# IOIO.net
KiCad netlist of a schematic drawn in EAGLE
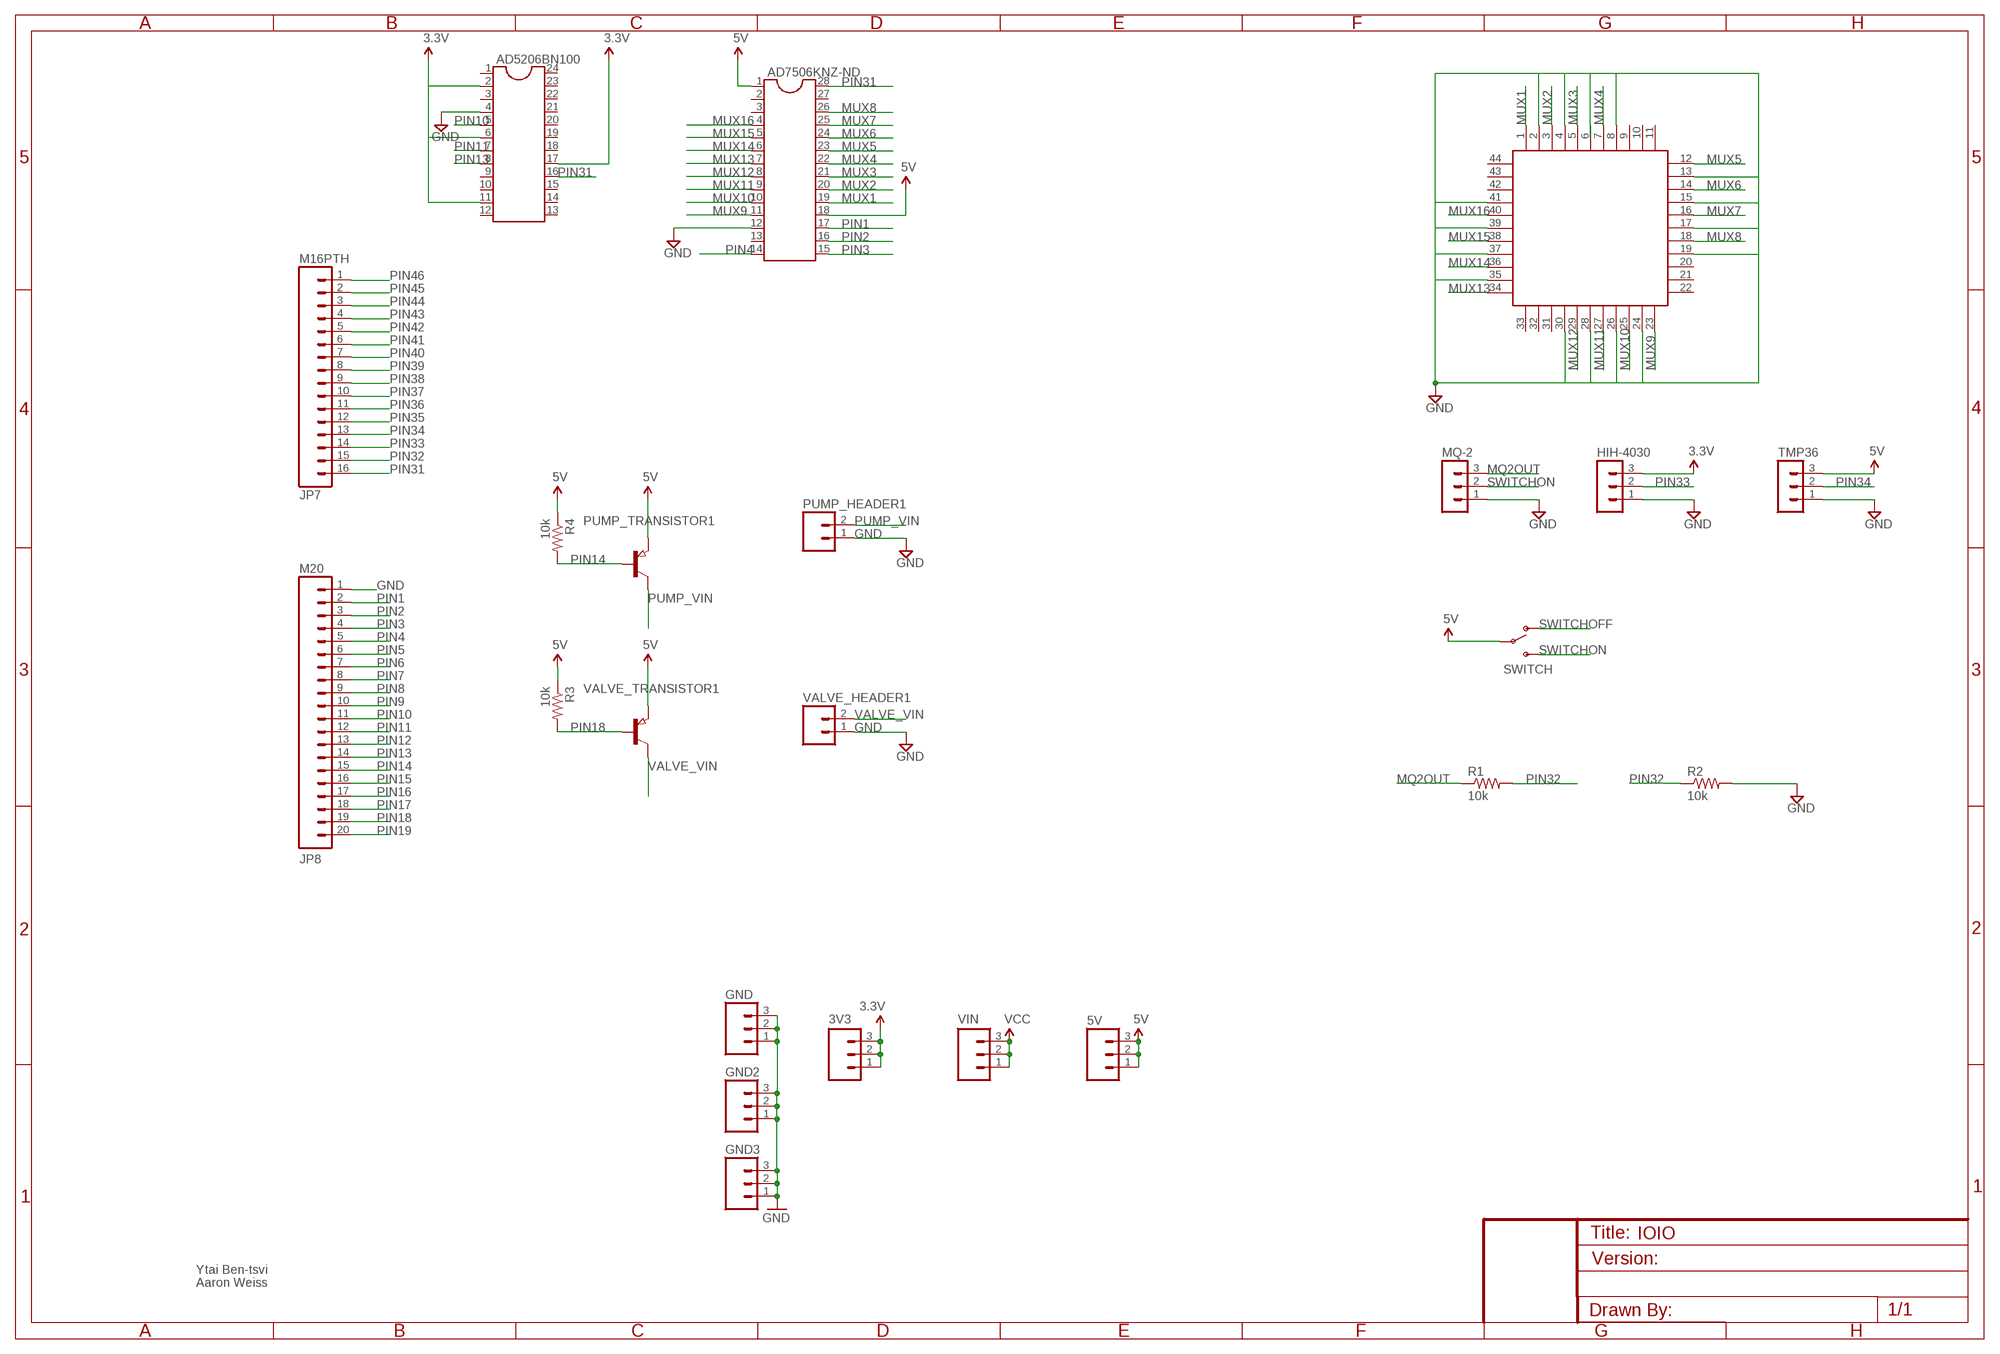
[diagram p0: schematic, sheet 1]

(export (version "E")
  (design (tool "Eeschema 10.0.6"))
  (components
    (comp (ref "3V3")
      (value "M03PTH")
      (footprint "eagle-import:1X03")
      (libsource (lib "eagle-import") (part "M03PTH"))
    )
    (comp (ref "5V")
      (value "M03PTH")
      (footprint "eagle-import:1X03")
      (libsource (lib "eagle-import") (part "M03PTH"))
    )
    (comp (ref "AD5206BN100")
      (value "DIL24-3")
      (footprint "eagle-import:DIL24-3")
      (libsource (lib "eagle-import") (part "DIL24-3"))
    )
    (comp (ref "AD7506KNZ-ND")
      (value "DIL28")
      (footprint "eagle-import:DIL28-6")
      (libsource (lib "eagle-import") (part "DIL28"))
    )
    (comp (ref "GND")
      (value "M03PTH")
      (footprint "eagle-import:1X03")
      (libsource (lib "eagle-import") (part "M03PTH"))
    )
    (comp (ref "GND2")
      (value "M03PTH")
      (footprint "eagle-import:1X03")
      (libsource (lib "eagle-import") (part "M03PTH"))
    )
    (comp (ref "GND3")
      (value "M03PTH")
      (footprint "eagle-import:1X03")
      (libsource (lib "eagle-import") (part "M03PTH"))
    )
    (comp (ref "HIH-4030")
      (value "MA03-1")
      (footprint "eagle-import:MA03-1")
      (libsource (lib "eagle-import") (part "MA03-1"))
    )
    (comp (ref "JP7")
      (value "M16PTH")
      (footprint "eagle-import:1X16")
      (libsource (lib "eagle-import") (part "M16PTH"))
    )
    (comp (ref "JP8")
      (value "M20")
      (footprint "eagle-import:1X20")
      (libsource (lib "eagle-import") (part "M20"))
    )
    (comp (ref "MQ-2")
      (value "MA03-1")
      (footprint "eagle-import:MA03-1")
      (libsource (lib "eagle-import") (part "MA03-1"))
    )
    (comp (ref "PUMP_HEADER1")
      (value "M02PTH")
      (footprint "eagle-import:1X02")
      (libsource (lib "eagle-import") (part "M02PTH"))
    )
    (comp (ref "PUMP_TRANSISTOR1")
      (value "PNP-TRANSISTOR_SOT23")
      (footprint "eagle-import:SOT23")
      (libsource (lib "eagle-import") (part "PNP-TRANSISTOR_SOT23"))
    )
    (comp (ref "R1")
      (value "10k")
      (footprint "eagle-import:0207_7")
      (libsource (lib "eagle-import") (part "R-US_0207/7"))
    )
    (comp (ref "R2")
      (value "10k")
      (footprint "eagle-import:0207_7")
      (libsource (lib "eagle-import") (part "R-US_0207/7"))
    )
    (comp (ref "R3")
      (value "10k")
      (footprint "eagle-import:M2012")
      (libsource (lib "eagle-import") (part "R-US_M2012"))
    )
    (comp (ref "R4")
      (value "10k")
      (footprint "eagle-import:M2012")
      (libsource (lib "eagle-import") (part "R-US_M2012"))
    )
    (comp (ref "SWITCH")
      (value "SWITCH-SPSTPTH")
      (footprint "eagle-import:SWITCH-SPDT")
      (libsource (lib "eagle-import") (part "SWITCH-SPSTPTH"))
    )
    (comp (ref "TMP36")
      (value "MA03-1")
      (footprint "eagle-import:MA03-1")
      (libsource (lib "eagle-import") (part "MA03-1"))
    )
    (comp (ref "U$1")
      (value "S44")
      (footprint "eagle-import:S44")
      (libsource (lib "eagle-import") (part "S44"))
    )
    (comp (ref "VALVE_HEADER1")
      (value "M02PTH")
      (footprint "eagle-import:1X02")
      (libsource (lib "eagle-import") (part "M02PTH"))
    )
    (comp (ref "VALVE_TRANSISTOR1")
      (value "PNP-TRANSISTOR_SOT23")
      (footprint "eagle-import:SOT23")
      (libsource (lib "eagle-import") (part "PNP-TRANSISTOR_SOT23"))
    )
    (comp (ref "VIN")
      (value "M03PTH")
      (footprint "eagle-import:1X03")
      (libsource (lib "eagle-import") (part "M03PTH"))
    )
  )
  (nets
    (net (code "1") (name "/MQ2OUT") (class "Default")
      (node (ref "MQ-2") (pin "3") (pinfunction "3_3") (pintype "passive"))
      (node (ref "R1") (pin "1") (pinfunction "1_1") (pintype "passive"))
    )
    (net (code "2") (name "/MUX1") (class "Default")
      (node (ref "AD7506KNZ-ND") (pin "19") (pinfunction "19_19") (pintype "passive"))
      (node (ref "U$1") (pin "1") (pinfunction "P$1_1") (pintype "bidirectional"))
    )
    (net (code "3") (name "/MUX2") (class "Default")
      (node (ref "AD7506KNZ-ND") (pin "20") (pinfunction "20_20") (pintype "passive"))
      (node (ref "U$1") (pin "3") (pinfunction "P$3_3") (pintype "bidirectional"))
    )
    (net (code "4") (name "/MUX3") (class "Default")
      (node (ref "AD7506KNZ-ND") (pin "21") (pinfunction "21_21") (pintype "passive"))
      (node (ref "U$1") (pin "5") (pinfunction "P$5_5") (pintype "bidirectional"))
    )
    (net (code "5") (name "/MUX4") (class "Default")
      (node (ref "AD7506KNZ-ND") (pin "22") (pinfunction "22_22") (pintype "passive"))
      (node (ref "U$1") (pin "7") (pinfunction "P$7_7") (pintype "bidirectional"))
    )
    (net (code "6") (name "/MUX5") (class "Default")
      (node (ref "AD7506KNZ-ND") (pin "23") (pinfunction "23_23") (pintype "passive"))
      (node (ref "U$1") (pin "12") (pinfunction "P$12_12") (pintype "bidirectional"))
    )
    (net (code "7") (name "/MUX6") (class "Default")
      (node (ref "AD7506KNZ-ND") (pin "24") (pinfunction "24_24") (pintype "passive"))
      (node (ref "U$1") (pin "14") (pinfunction "P$14_14") (pintype "bidirectional"))
    )
    (net (code "8") (name "/MUX7") (class "Default")
      (node (ref "AD7506KNZ-ND") (pin "25") (pinfunction "25_25") (pintype "passive"))
      (node (ref "U$1") (pin "16") (pinfunction "P$16_16") (pintype "bidirectional"))
    )
    (net (code "9") (name "/MUX8") (class "Default")
      (node (ref "AD7506KNZ-ND") (pin "26") (pinfunction "26_26") (pintype "passive"))
      (node (ref "U$1") (pin "18") (pinfunction "P$18_18") (pintype "bidirectional"))
    )
    (net (code "10") (name "/MUX9") (class "Default")
      (node (ref "AD7506KNZ-ND") (pin "11") (pinfunction "11_11") (pintype "passive"))
      (node (ref "U$1") (pin "23") (pinfunction "P$23_23") (pintype "bidirectional"))
    )
    (net (code "11") (name "/MUX10") (class "Default")
      (node (ref "AD7506KNZ-ND") (pin "10") (pinfunction "10_10") (pintype "passive"))
      (node (ref "U$1") (pin "25") (pinfunction "P$25_25") (pintype "bidirectional"))
    )
    (net (code "12") (name "/MUX11") (class "Default")
      (node (ref "AD7506KNZ-ND") (pin "9") (pinfunction "9_9") (pintype "passive"))
      (node (ref "U$1") (pin "27") (pinfunction "P$27_27") (pintype "bidirectional"))
    )
    (net (code "13") (name "/MUX12") (class "Default")
      (node (ref "AD7506KNZ-ND") (pin "8") (pinfunction "8_8") (pintype "passive"))
      (node (ref "U$1") (pin "29") (pinfunction "P$29_29") (pintype "bidirectional"))
    )
    (net (code "14") (name "/MUX13") (class "Default")
      (node (ref "AD7506KNZ-ND") (pin "7") (pinfunction "7_7") (pintype "passive"))
      (node (ref "U$1") (pin "34") (pinfunction "P$34_34") (pintype "bidirectional"))
    )
    (net (code "15") (name "/MUX14") (class "Default")
      (node (ref "AD7506KNZ-ND") (pin "6") (pinfunction "6_6") (pintype "passive"))
      (node (ref "U$1") (pin "36") (pinfunction "P$36_36") (pintype "bidirectional"))
    )
    (net (code "16") (name "/MUX15") (class "Default")
      (node (ref "AD7506KNZ-ND") (pin "5") (pinfunction "5_5") (pintype "passive"))
      (node (ref "U$1") (pin "38") (pinfunction "P$38_38") (pintype "bidirectional"))
    )
    (net (code "17") (name "/MUX16") (class "Default")
      (node (ref "AD7506KNZ-ND") (pin "4") (pinfunction "4_4") (pintype "passive"))
      (node (ref "U$1") (pin "40") (pinfunction "P$40_40") (pintype "bidirectional"))
    )
    (net (code "18") (name "/PIN1") (class "Default")
      (node (ref "AD7506KNZ-ND") (pin "17") (pinfunction "17_17") (pintype "passive"))
      (node (ref "JP8") (pin "2") (pinfunction "2_2") (pintype "passive"))
    )
    (net (code "19") (name "/PIN2") (class "Default")
      (node (ref "AD7506KNZ-ND") (pin "16") (pinfunction "16_16") (pintype "passive"))
      (node (ref "JP8") (pin "3") (pinfunction "3_3") (pintype "passive"))
    )
    (net (code "20") (name "/PIN3") (class "Default")
      (node (ref "AD7506KNZ-ND") (pin "15") (pinfunction "15_15") (pintype "passive"))
      (node (ref "JP8") (pin "4") (pinfunction "4_4") (pintype "passive"))
    )
    (net (code "21") (name "/PIN4") (class "Default")
      (node (ref "AD7506KNZ-ND") (pin "14") (pinfunction "14_14") (pintype "passive"))
      (node (ref "JP8") (pin "5") (pinfunction "5_5") (pintype "passive"))
    )
    (net (code "22") (name "/PIN5") (class "Default")
      (node (ref "JP8") (pin "6") (pinfunction "6_6") (pintype "passive"))
    )
    (net (code "23") (name "/PIN6") (class "Default")
      (node (ref "JP8") (pin "7") (pinfunction "7_7") (pintype "passive"))
    )
    (net (code "24") (name "/PIN7") (class "Default")
      (node (ref "JP8") (pin "8") (pinfunction "8_8") (pintype "passive"))
    )
    (net (code "25") (name "/PIN8") (class "Default")
      (node (ref "JP8") (pin "9") (pinfunction "9_9") (pintype "passive"))
    )
    (net (code "26") (name "/PIN9") (class "Default")
      (node (ref "JP8") (pin "10") (pinfunction "10_10") (pintype "passive"))
    )
    (net (code "27") (name "/PIN10") (class "Default")
      (node (ref "AD5206BN100") (pin "5") (pinfunction "5_5") (pintype "passive"))
      (node (ref "JP8") (pin "11") (pinfunction "11_11") (pintype "passive"))
    )
    (net (code "28") (name "/PIN11") (class "Default")
      (node (ref "AD5206BN100") (pin "7") (pinfunction "7_7") (pintype "passive"))
      (node (ref "JP8") (pin "12") (pinfunction "12_12") (pintype "passive"))
    )
    (net (code "29") (name "/PIN12") (class "Default")
      (node (ref "JP8") (pin "13") (pinfunction "13_13") (pintype "passive"))
    )
    (net (code "30") (name "/PIN13") (class "Default")
      (node (ref "AD5206BN100") (pin "8") (pinfunction "8_8") (pintype "passive"))
      (node (ref "JP8") (pin "14") (pinfunction "14_14") (pintype "passive"))
    )
    (net (code "31") (name "/PIN14") (class "Default")
      (node (ref "JP8") (pin "15") (pinfunction "15_15") (pintype "passive"))
      (node (ref "PUMP_TRANSISTOR1") (pin "1") (pinfunction "B_1") (pintype "passive"))
      (node (ref "R4") (pin "2") (pinfunction "2_2") (pintype "passive"))
    )
    (net (code "32") (name "/PIN15") (class "Default")
      (node (ref "JP8") (pin "16") (pinfunction "16_16") (pintype "passive"))
    )
    (net (code "33") (name "/PIN16") (class "Default")
      (node (ref "JP8") (pin "17") (pinfunction "17_17") (pintype "passive"))
    )
    (net (code "34") (name "/PIN17") (class "Default")
      (node (ref "JP8") (pin "18") (pinfunction "18_18") (pintype "passive"))
    )
    (net (code "35") (name "/PIN18") (class "Default")
      (node (ref "JP8") (pin "19") (pinfunction "19_19") (pintype "passive"))
      (node (ref "R3") (pin "2") (pinfunction "2_2") (pintype "passive"))
      (node (ref "VALVE_TRANSISTOR1") (pin "1") (pinfunction "B_1") (pintype "passive"))
    )
    (net (code "36") (name "/PIN19") (class "Default")
      (node (ref "JP8") (pin "20") (pinfunction "20_20") (pintype "passive"))
    )
    (net (code "37") (name "/PIN31") (class "Default")
      (node (ref "AD5206BN100") (pin "16") (pinfunction "16_16") (pintype "passive"))
      (node (ref "AD7506KNZ-ND") (pin "28") (pinfunction "28_28") (pintype "passive"))
      (node (ref "JP7") (pin "16") (pinfunction "16_16") (pintype "passive"))
    )
    (net (code "38") (name "/PIN32") (class "Default")
      (node (ref "JP7") (pin "15") (pinfunction "15_15") (pintype "passive"))
      (node (ref "R1") (pin "2") (pinfunction "2_2") (pintype "passive"))
      (node (ref "R2") (pin "1") (pinfunction "1_1") (pintype "passive"))
    )
    (net (code "39") (name "/PIN33") (class "Default")
      (node (ref "HIH-4030") (pin "2") (pinfunction "2_2") (pintype "passive"))
      (node (ref "JP7") (pin "14") (pinfunction "14_14") (pintype "passive"))
    )
    (net (code "40") (name "/PIN34") (class "Default")
      (node (ref "JP7") (pin "13") (pinfunction "13_13") (pintype "passive"))
      (node (ref "TMP36") (pin "2") (pinfunction "2_2") (pintype "passive"))
    )
    (net (code "41") (name "/PIN35") (class "Default")
      (node (ref "JP7") (pin "12") (pinfunction "12_12") (pintype "passive"))
    )
    (net (code "42") (name "/PIN36") (class "Default")
      (node (ref "JP7") (pin "11") (pinfunction "11_11") (pintype "passive"))
    )
    (net (code "43") (name "/PIN37") (class "Default")
      (node (ref "JP7") (pin "10") (pinfunction "10_10") (pintype "passive"))
    )
    (net (code "44") (name "/PIN38") (class "Default")
      (node (ref "JP7") (pin "9") (pinfunction "9_9") (pintype "passive"))
    )
    (net (code "45") (name "/PIN39") (class "Default")
      (node (ref "JP7") (pin "8") (pinfunction "8_8") (pintype "passive"))
    )
    (net (code "46") (name "/PIN40") (class "Default")
      (node (ref "JP7") (pin "7") (pinfunction "7_7") (pintype "passive"))
    )
    (net (code "47") (name "/PIN41") (class "Default")
      (node (ref "JP7") (pin "6") (pinfunction "6_6") (pintype "passive"))
    )
    (net (code "48") (name "/PIN42") (class "Default")
      (node (ref "JP7") (pin "5") (pinfunction "5_5") (pintype "passive"))
    )
    (net (code "49") (name "/PIN43") (class "Default")
      (node (ref "JP7") (pin "4") (pinfunction "4_4") (pintype "passive"))
    )
    (net (code "50") (name "/PIN44") (class "Default")
      (node (ref "JP7") (pin "3") (pinfunction "3_3") (pintype "passive"))
    )
    (net (code "51") (name "/PIN45") (class "Default")
      (node (ref "JP7") (pin "2") (pinfunction "2_2") (pintype "passive"))
    )
    (net (code "52") (name "/PIN46") (class "Default")
      (node (ref "JP7") (pin "1") (pinfunction "1_1") (pintype "passive"))
    )
    (net (code "53") (name "/PUMP_VIN") (class "Default")
      (node (ref "PUMP_HEADER1") (pin "2") (pinfunction "2_2") (pintype "passive"))
      (node (ref "PUMP_TRANSISTOR1") (pin "3") (pinfunction "C_3") (pintype "passive"))
    )
    (net (code "54") (name "/SWITCHOFF") (class "Default")
      (node (ref "SWITCH") (pin "1") (pinfunction "O_1") (pintype "passive"))
    )
    (net (code "55") (name "/SWITCHON") (class "Default")
      (node (ref "MQ-2") (pin "2") (pinfunction "2_2") (pintype "passive"))
      (node (ref "SWITCH") (pin "3") (pinfunction "S_3") (pintype "passive"))
    )
    (net (code "56") (name "/VALVE_VIN") (class "Default")
      (node (ref "VALVE_HEADER1") (pin "2") (pinfunction "2_2") (pintype "passive"))
      (node (ref "VALVE_TRANSISTOR1") (pin "3") (pinfunction "C_3") (pintype "passive"))
    )
    (net (code "57") (name "3.3V") (class "Default")
      (node (ref "3V3") (pin "1") (pinfunction "1_1") (pintype "passive"))
      (node (ref "3V3") (pin "2") (pinfunction "2_2") (pintype "passive"))
      (node (ref "3V3") (pin "3") (pinfunction "3_3") (pintype "passive"))
      (node (ref "AD5206BN100") (pin "11") (pinfunction "11_11") (pintype "passive"))
      (node (ref "AD5206BN100") (pin "17") (pinfunction "17_17") (pintype "passive"))
      (node (ref "AD5206BN100") (pin "2") (pinfunction "2_2") (pintype "passive"))
      (node (ref "AD5206BN100") (pin "6") (pinfunction "6_6") (pintype "passive"))
      (node (ref "HIH-4030") (pin "3") (pinfunction "3_3") (pintype "passive"))
    )
    (net (code "58") (name "5V") (class "Default")
      (node (ref "5V") (pin "1") (pinfunction "1_1") (pintype "passive"))
      (node (ref "5V") (pin "2") (pinfunction "2_2") (pintype "passive"))
      (node (ref "5V") (pin "3") (pinfunction "3_3") (pintype "passive"))
      (node (ref "AD7506KNZ-ND") (pin "1") (pinfunction "1_1") (pintype "passive"))
      (node (ref "AD7506KNZ-ND") (pin "18") (pinfunction "18_18") (pintype "passive"))
      (node (ref "PUMP_TRANSISTOR1") (pin "2") (pinfunction "E_2") (pintype "passive"))
      (node (ref "R3") (pin "1") (pinfunction "1_1") (pintype "passive"))
      (node (ref "R4") (pin "1") (pinfunction "1_1") (pintype "passive"))
      (node (ref "SWITCH") (pin "2") (pinfunction "P_2") (pintype "passive"))
      (node (ref "TMP36") (pin "3") (pinfunction "3_3") (pintype "passive"))
      (node (ref "VALVE_TRANSISTOR1") (pin "2") (pinfunction "E_2") (pintype "passive"))
    )
    (net (code "59") (name "GND") (class "Default")
      (node (ref "AD5206BN100") (pin "4") (pinfunction "4_4") (pintype "passive"))
      (node (ref "AD7506KNZ-ND") (pin "12") (pinfunction "12_12") (pintype "passive"))
      (node (ref "GND") (pin "1") (pinfunction "1_1") (pintype "passive"))
      (node (ref "GND") (pin "2") (pinfunction "2_2") (pintype "passive"))
      (node (ref "GND") (pin "3") (pinfunction "3_3") (pintype "passive"))
      (node (ref "GND2") (pin "1") (pinfunction "1_1") (pintype "passive"))
      (node (ref "GND2") (pin "2") (pinfunction "2_2") (pintype "passive"))
      (node (ref "GND2") (pin "3") (pinfunction "3_3") (pintype "passive"))
      (node (ref "GND3") (pin "1") (pinfunction "1_1") (pintype "passive"))
      (node (ref "GND3") (pin "2") (pinfunction "2_2") (pintype "passive"))
      (node (ref "GND3") (pin "3") (pinfunction "3_3") (pintype "passive"))
      (node (ref "HIH-4030") (pin "1") (pinfunction "1_1") (pintype "passive"))
      (node (ref "JP8") (pin "1") (pinfunction "1_1") (pintype "passive"))
      (node (ref "MQ-2") (pin "1") (pinfunction "1_1") (pintype "passive"))
      (node (ref "PUMP_HEADER1") (pin "1") (pinfunction "1_1") (pintype "passive"))
      (node (ref "R2") (pin "2") (pinfunction "2_2") (pintype "passive"))
      (node (ref "TMP36") (pin "1") (pinfunction "1_1") (pintype "passive"))
      (node (ref "U$1") (pin "13") (pinfunction "P$13_13") (pintype "bidirectional"))
      (node (ref "U$1") (pin "15") (pinfunction "P$15_15") (pintype "bidirectional"))
      (node (ref "U$1") (pin "17") (pinfunction "P$17_17") (pintype "bidirectional"))
      (node (ref "U$1") (pin "19") (pinfunction "P$19_19") (pintype "bidirectional"))
      (node (ref "U$1") (pin "2") (pinfunction "P$2_2") (pintype "bidirectional"))
      (node (ref "U$1") (pin "24") (pinfunction "P$24_24") (pintype "bidirectional"))
      (node (ref "U$1") (pin "26") (pinfunction "P$26_26") (pintype "bidirectional"))
      (node (ref "U$1") (pin "28") (pinfunction "P$28_28") (pintype "bidirectional"))
      (node (ref "U$1") (pin "30") (pinfunction "P$30_30") (pintype "bidirectional"))
      (node (ref "U$1") (pin "35") (pinfunction "P$35_35") (pintype "bidirectional"))
      (node (ref "U$1") (pin "37") (pinfunction "P$37_37") (pintype "bidirectional"))
      (node (ref "U$1") (pin "39") (pinfunction "P$39_39") (pintype "bidirectional"))
      (node (ref "U$1") (pin "4") (pinfunction "P$4_4") (pintype "bidirectional"))
      (node (ref "U$1") (pin "41") (pinfunction "P$41_41") (pintype "bidirectional"))
      (node (ref "U$1") (pin "8") (pinfunction "P$8_8") (pintype "bidirectional"))
      (node (ref "VALVE_HEADER1") (pin "1") (pinfunction "1_1") (pintype "passive"))
    )
    (net (code "60") (name "VCC") (class "Default")
      (node (ref "VIN") (pin "1") (pinfunction "1_1") (pintype "passive"))
      (node (ref "VIN") (pin "2") (pinfunction "2_2") (pintype "passive"))
      (node (ref "VIN") (pin "3") (pinfunction "3_3") (pintype "passive"))
    )
    (net (code "61") (name "unconnected-(AD5206BN100-Pad1)") (class "Default")
      (node (ref "AD5206BN100") (pin "1") (pinfunction "1_1") (pintype "passive"))
    )
    (net (code "62") (name "unconnected-(AD5206BN100-Pad3)") (class "Default")
      (node (ref "AD5206BN100") (pin "3") (pinfunction "3_3") (pintype "passive"))
    )
    (net (code "63") (name "unconnected-(AD5206BN100-Pad9)") (class "Default")
      (node (ref "AD5206BN100") (pin "9") (pinfunction "9_9") (pintype "passive"))
    )
    (net (code "64") (name "unconnected-(AD5206BN100-Pad10)") (class "Default")
      (node (ref "AD5206BN100") (pin "10") (pinfunction "10_10") (pintype "passive"))
    )
    (net (code "65") (name "unconnected-(AD5206BN100-Pad12)") (class "Default")
      (node (ref "AD5206BN100") (pin "12") (pinfunction "12_12") (pintype "passive"))
    )
    (net (code "66") (name "unconnected-(AD5206BN100-Pad13)") (class "Default")
      (node (ref "AD5206BN100") (pin "13") (pinfunction "13_13") (pintype "passive"))
    )
    (net (code "67") (name "unconnected-(AD5206BN100-Pad14)") (class "Default")
      (node (ref "AD5206BN100") (pin "14") (pinfunction "14_14") (pintype "passive"))
    )
    (net (code "68") (name "unconnected-(AD5206BN100-Pad15)") (class "Default")
      (node (ref "AD5206BN100") (pin "15") (pinfunction "15_15") (pintype "passive"))
    )
    (net (code "69") (name "unconnected-(AD5206BN100-Pad18)") (class "Default")
      (node (ref "AD5206BN100") (pin "18") (pinfunction "18_18") (pintype "passive"))
    )
    (net (code "70") (name "unconnected-(AD5206BN100-Pad19)") (class "Default")
      (node (ref "AD5206BN100") (pin "19") (pinfunction "19_19") (pintype "passive"))
    )
    (net (code "71") (name "unconnected-(AD5206BN100-Pad20)") (class "Default")
      (node (ref "AD5206BN100") (pin "20") (pinfunction "20_20") (pintype "passive"))
    )
    (net (code "72") (name "unconnected-(AD5206BN100-Pad21)") (class "Default")
      (node (ref "AD5206BN100") (pin "21") (pinfunction "21_21") (pintype "passive"))
    )
    (net (code "73") (name "unconnected-(AD5206BN100-Pad22)") (class "Default")
      (node (ref "AD5206BN100") (pin "22") (pinfunction "22_22") (pintype "passive"))
    )
    (net (code "74") (name "unconnected-(AD5206BN100-Pad23)") (class "Default")
      (node (ref "AD5206BN100") (pin "23") (pinfunction "23_23") (pintype "passive"))
    )
    (net (code "75") (name "unconnected-(AD5206BN100-Pad24)") (class "Default")
      (node (ref "AD5206BN100") (pin "24") (pinfunction "24_24") (pintype "passive"))
    )
    (net (code "76") (name "unconnected-(AD7506KNZ-ND-Pad2)") (class "Default")
      (node (ref "AD7506KNZ-ND") (pin "2") (pinfunction "2_2") (pintype "passive"))
    )
    (net (code "77") (name "unconnected-(AD7506KNZ-ND-Pad3)") (class "Default")
      (node (ref "AD7506KNZ-ND") (pin "3") (pinfunction "3_3") (pintype "passive"))
    )
    (net (code "78") (name "unconnected-(AD7506KNZ-ND-Pad13)") (class "Default")
      (node (ref "AD7506KNZ-ND") (pin "13") (pinfunction "13_13") (pintype "passive"))
    )
    (net (code "79") (name "unconnected-(AD7506KNZ-ND-Pad27)") (class "Default")
      (node (ref "AD7506KNZ-ND") (pin "27") (pinfunction "27_27") (pintype "passive"))
    )
    (net (code "80") (name "unconnected-(U$1-P$6-Pad6)") (class "Default")
      (node (ref "U$1") (pin "6") (pinfunction "P$6_6") (pintype "bidirectional"))
    )
    (net (code "81") (name "unconnected-(U$1-P$9-Pad9)") (class "Default")
      (node (ref "U$1") (pin "9") (pinfunction "P$9_9") (pintype "bidirectional"))
    )
    (net (code "82") (name "unconnected-(U$1-P$10-Pad10)") (class "Default")
      (node (ref "U$1") (pin "10") (pinfunction "P$10_10") (pintype "bidirectional"))
    )
    (net (code "83") (name "unconnected-(U$1-P$11-Pad11)") (class "Default")
      (node (ref "U$1") (pin "11") (pinfunction "P$11_11") (pintype "bidirectional"))
    )
    (net (code "84") (name "unconnected-(U$1-P$20-Pad20)") (class "Default")
      (node (ref "U$1") (pin "20") (pinfunction "P$20_20") (pintype "bidirectional"))
    )
    (net (code "85") (name "unconnected-(U$1-P$21-Pad21)") (class "Default")
      (node (ref "U$1") (pin "21") (pinfunction "P$21_21") (pintype "bidirectional"))
    )
    (net (code "86") (name "unconnected-(U$1-P$22-Pad22)") (class "Default")
      (node (ref "U$1") (pin "22") (pinfunction "P$22_22") (pintype "bidirectional"))
    )
    (net (code "87") (name "unconnected-(U$1-P$31-Pad31)") (class "Default")
      (node (ref "U$1") (pin "31") (pinfunction "P$31_31") (pintype "bidirectional"))
    )
    (net (code "88") (name "unconnected-(U$1-P$32-Pad32)") (class "Default")
      (node (ref "U$1") (pin "32") (pinfunction "P$32_32") (pintype "bidirectional"))
    )
    (net (code "89") (name "unconnected-(U$1-P$33-Pad33)") (class "Default")
      (node (ref "U$1") (pin "33") (pinfunction "P$33_33") (pintype "bidirectional"))
    )
    (net (code "90") (name "unconnected-(U$1-P$42-Pad42)") (class "Default")
      (node (ref "U$1") (pin "42") (pinfunction "P$42_42") (pintype "bidirectional"))
    )
    (net (code "91") (name "unconnected-(U$1-P$43-Pad43)") (class "Default")
      (node (ref "U$1") (pin "43") (pinfunction "P$43_43") (pintype "bidirectional"))
    )
    (net (code "92") (name "unconnected-(U$1-P$44-Pad44)") (class "Default")
      (node (ref "U$1") (pin "44") (pinfunction "P$44_44") (pintype "bidirectional"))
    )
  )
)
